# CLKB_power_regulators.net
KiCad netlist of a schematic drawn in Altium Designer
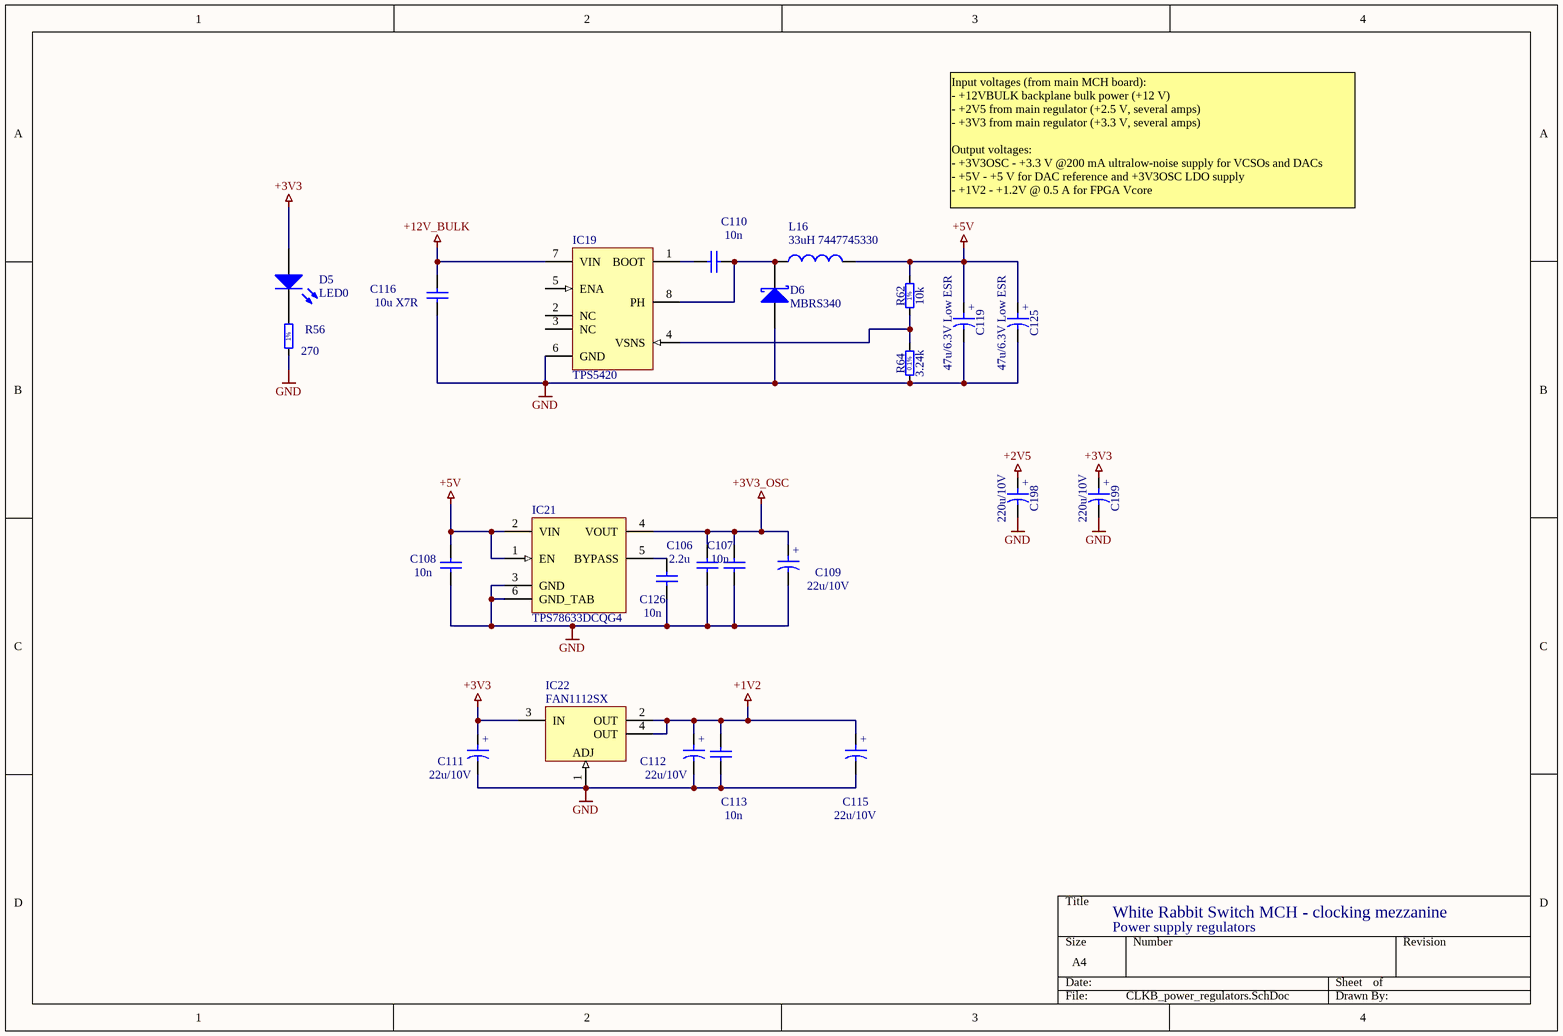
[diagram p0: CLKB_power_regulators.SchDoc]

(export (version "E")
  (design (tool "Eeschema 10.0.6"))
  (components
    (comp (ref "C106")
      (value "2.2u")
      (footprint "CAPC2012X135N")
      (description "Non-polarised capacitor")
      (fields
        (field (name "PART NUMBER") "CC0805_2.2UF_16V_10%_X7R")
        (field (name "VOLTAGE") "16V")
        (field (name "AUTHOR") "CERN DEM JLC")
      )
      (libsource (lib "Capacitors") (part "Capacitor - non polarized"))
    )
    (comp (ref "C107")
      (value "10n")
      (footprint "CAPC1608X87N")
      (description "Non-polarised capacitor")
      (fields
        (field (name "PART NUMBER") "CC0603_10NF_50V_10%_X7R")
        (field (name "VOLTAGE") "50V")
        (field (name "AUTHOR") "CERN DEM JLC")
      )
      (libsource (lib "Capacitors") (part "Capacitor - non polarized"))
    )
    (comp (ref "C108")
      (value "10n")
      (footprint "CAPC1608X87N")
      (description "Non-polarised capacitor")
      (fields
        (field (name "PART NUMBER") "CC0603_10NF_50V_10%_X7R")
        (field (name "VOLTAGE") "50V")
        (field (name "AUTHOR") "CERN DEM JLC")
      )
      (libsource (lib "Capacitors") (part "Capacitor - non polarized"))
    )
    (comp (ref "C109")
      (value "22u/10V")
      (footprint "CAPMP3216X180N")
      (description "Polarised capacitor")
      (fields
        (field (name "PART NUMBER") "CTE3216-18_22UF_10V_10%")
        (field (name "VOLTAGE") "10V")
        (field (name "AUTHOR") "CERN DEM JLC")
      )
      (libsource (lib "Capacitors") (part "Capacitor - polarized"))
    )
    (comp (ref "C110")
      (value "10n")
      (footprint "CAPC1608X87N")
      (description "Non-polarised capacitor")
      (fields
        (field (name "PART NUMBER") "CC0603_10NF_50V_10%_X7R")
        (field (name "VOLTAGE") "50V")
        (field (name "AUTHOR") "CERN DEM JLC")
      )
      (libsource (lib "Capacitors") (part "Capacitor - non polarized"))
    )
    (comp (ref "C111")
      (value "22u/10V")
      (footprint "CAPMP3216X180N")
      (description "Polarised capacitor")
      (fields
        (field (name "PART NUMBER") "CTE3216-18_22UF_10V_10%")
        (field (name "VOLTAGE") "10V")
        (field (name "AUTHOR") "CERN DEM JLC")
      )
      (libsource (lib "Capacitors") (part "Capacitor - polarized"))
    )
    (comp (ref "C112")
      (value "10n")
      (footprint "CAPC1608X87N")
      (description "Non-polarised capacitor")
      (fields
        (field (name "PART NUMBER") "CC0603_10NF_50V_10%_X7R")
        (field (name "VOLTAGE") "50V")
        (field (name "AUTHOR") "CERN DEM JLC")
      )
      (libsource (lib "Capacitors") (part "Capacitor - non polarized"))
    )
    (comp (ref "C113")
      (value "22u/10V")
      (footprint "CAPMP3216X180N")
      (description "Polarised capacitor")
      (fields
        (field (name "PART NUMBER") "CTE3216-18_22UF_10V_10%")
        (field (name "VOLTAGE") "10V")
        (field (name "AUTHOR") "CERN DEM JLC")
      )
      (libsource (lib "Capacitors") (part "Capacitor - polarized"))
    )
    (comp (ref "C115")
      (value "22u/10V")
      (footprint "CAPMP3216X180N")
      (description "Polarised capacitor")
      (fields
        (field (name "PART NUMBER") "CTE3216-18_22UF_10V_10%")
        (field (name "VOLTAGE") "10V")
        (field (name "AUTHOR") "CERN DEM JLC")
      )
      (libsource (lib "Capacitors") (part "Capacitor - polarized"))
    )
    (comp (ref "C116")
      (value "10u X7R")
      (footprint "CAPC3216X140N")
      (description "Non-polarised capacitor")
      (fields
        (field (name "PART NUMBER") "CC1206_10UF_16V_10%_X7R")
        (field (name "VOLTAGE") "16V")
        (field (name "AUTHOR") "CERN DEM JLC")
      )
      (libsource (lib "Capacitors") (part "Capacitor - non polarized"))
    )
    (comp (ref "C119")
      (value "47u/6.3V Low ESR")
      (footprint "CAPMP3528X210N")
      (description "Polarised capacitor")
      (fields
        (field (name "PART NUMBER") "CTE3528-21_47UF_6.3V_10%_LESR0250")
        (field (name "VOLTAGE") "6.3V")
        (field (name "AUTHOR") "CERN DEM JLC")
      )
      (libsource (lib "Capacitors") (part "Capacitor - polarized"))
    )
    (comp (ref "C125")
      (value "47u/6.3V Low ESR")
      (footprint "CAPMP3528X210N")
      (description "Polarised capacitor")
      (fields
        (field (name "PART NUMBER") "CTE3528-21_47UF_6.3V_10%_LESR0250")
        (field (name "VOLTAGE") "6.3V")
        (field (name "AUTHOR") "CERN DEM JLC")
      )
      (libsource (lib "Capacitors") (part "Capacitor - polarized"))
    )
    (comp (ref "C126")
      (value "10n")
      (footprint "CAPC1608X87N")
      (description "Non-polarised capacitor")
      (fields
        (field (name "PART NUMBER") "CC0603_10NF_50V_10%_X7R")
        (field (name "VOLTAGE") "50V")
        (field (name "AUTHOR") "CERN DEM JLC")
      )
      (libsource (lib "Capacitors") (part "Capacitor - non polarized"))
    )
    (comp (ref "C198")
      (value "220u/10V")
      (footprint "CAPMP7343X430N")
      (description "Polarised capacitor")
      (fields
        (field (name "PART NUMBER") "CTE7343-43_220UF_10V_10%_LESR0050")
        (field (name "VOLTAGE") "10V")
        (field (name "AUTHOR") "CERN DEM JLC")
      )
      (libsource (lib "Capacitors") (part "Capacitor - polarized"))
    )
    (comp (ref "C199")
      (value "220u/10V")
      (footprint "CAPMP7343X430N")
      (description "Polarised capacitor")
      (fields
        (field (name "PART NUMBER") "CTE7343-43_220UF_10V_10%_LESR0050")
        (field (name "VOLTAGE") "10V")
        (field (name "AUTHOR") "CERN DEM JLC")
      )
      (libsource (lib "Capacitors") (part "Capacitor - polarized"))
    )
    (comp (ref "D5")
      (value "LED0")
      (footprint "CD1608-0603")
      (description "Red chip LED")
      (fields (field (name "PUBLISHER") "Altium Limited"))
      (libsource (lib "Miscellaneous Devices") (part "LED0"))
    )
    (comp (ref "D6")
      (value "MBRS340")
      (footprint "SMB")
      (description "Schottky Diode")
      (fields (field (name "PUBLISHER") "Altium Limited"))
      (libsource (lib "wr_switch") (part "D Schottky"))
    )
    (comp (ref "IC19")
      (value "TPS5420")
      (footprint "SOIC127P600-8AL")
      (description "Step-down switchmode converter")
      (libsource (lib "wr_switch") (part "TPS5420"))
    )
    (comp (ref "IC21")
      (value "TPS78633DCQG4")
      (footprint "SOT223-6L")
      (description "TI low noise LDO, 1A load")
      (fields (field (name "Comment") "TPS78633"))
      (libsource (lib "wr_switch") (part "TPS786xx"))
    )
    (comp (ref "IC22")
      (value "FAN1112SX")
      (footprint "SOT223-4L")
      (description "Three-Terminal Adjustable Output Positive Voltage Regulator")
      (fields (field (name "PUBLISHER") "Altium Limited"))
      (libsource (lib "wr_switch") (part "1117"))
    )
    (comp (ref "L16")
      (value "33uH 7447745330")
      (footprint "L_VLCF5020")
      (description "Wuerth small footprint SMD power inductor")
      (libsource (lib "wr_switch") (part "L_WUERTH_744043"))
    )
    (comp (ref "R56")
      (value "270")
      (footprint "RESC1608X55N")
      (description "Resistor - 1%")
      (fields
        (field (name "PART NUMBER") "R0603_270R_1%_0.1W_100PPM")
        (field (name "POWER") "0.1W")
        (field (name "AUTHOR") "CERN DEM JLC")
      )
      (libsource (lib "Resistors") (part "Resistor - 1%"))
    )
    (comp (ref "R62")
      (value "10k")
      (footprint "RESC1608X55N")
      (description "Resistor - 1%")
      (fields
        (field (name "PART NUMBER") "R0603_10K_1%_0.1W_100PPM")
        (field (name "POWER") "0.1W")
        (field (name "AUTHOR") "CERN DEM JLC")
      )
      (libsource (lib "Resistors") (part "Resistor - 1%"))
    )
    (comp (ref "R64")
      (value "3.24k")
      (footprint "RESC1608X55N")
      (description "Resistor - 0.1%")
      (fields
        (field (name "PART NUMBER") "R0603_3K24_0.1%_0.063W_10PPM")
        (field (name "POWER") "0.063W")
        (field (name "AUTHOR") "CERN DEM JLC")
      )
      (libsource (lib "Resistors") (part "Resistor - 0.1%"))
    )
  )
  (nets
    (net (code "1") (name "+1V2") (class "Default")
      (node (ref "C112") (pin "2") (pinfunction "2_2") (pintype "passive"))
      (node (ref "C113") (pin "1") (pinfunction "1_1") (pintype "passive"))
      (node (ref "C115") (pin "1") (pinfunction "1_1") (pintype "passive"))
      (node (ref "IC22") (pin "2") (pinfunction "OUT_2") (pintype "power_in"))
      (node (ref "IC22") (pin "4") (pinfunction "OUT_4") (pintype "power_in"))
    )
    (net (code "2") (name "+2V5") (class "Default")
      (node (ref "C198") (pin "1") (pinfunction "1_1") (pintype "passive"))
    )
    (net (code "3") (name "+3V3") (class "Default")
      (node (ref "C111") (pin "1") (pinfunction "1_1") (pintype "passive"))
      (node (ref "C199") (pin "1") (pinfunction "1_1") (pintype "passive"))
      (node (ref "D5") (pin "1") (pinfunction "A_1") (pintype "passive"))
      (node (ref "IC22") (pin "3") (pinfunction "IN_3") (pintype "power_in"))
    )
    (net (code "4") (name "+3V3_OSC") (class "Default")
      (node (ref "C106") (pin "2") (pinfunction "2_2") (pintype "passive"))
      (node (ref "C107") (pin "2") (pinfunction "2_2") (pintype "passive"))
      (node (ref "C109") (pin "1") (pinfunction "1_1") (pintype "passive"))
      (node (ref "IC21") (pin "4") (pinfunction "VOUT_4") (pintype "power_in"))
    )
    (net (code "5") (name "+5V") (class "Default")
      (node (ref "C108") (pin "2") (pinfunction "2_2") (pintype "passive"))
      (node (ref "C119") (pin "1") (pinfunction "1_1") (pintype "passive"))
      (node (ref "C125") (pin "1") (pinfunction "1_1") (pintype "passive"))
      (node (ref "IC21") (pin "1") (pinfunction "EN_1") (pintype "input"))
      (node (ref "IC21") (pin "2") (pinfunction "VIN_2") (pintype "open_emitter"))
      (node (ref "L16") (pin "2") (pinfunction "2_2") (pintype "passive"))
      (node (ref "R62") (pin "2") (pinfunction "2_2") (pintype "passive"))
    )
    (net (code "6") (name "+12V_BULK") (class "Default")
      (node (ref "C116") (pin "2") (pinfunction "2_2") (pintype "passive"))
      (node (ref "IC19") (pin "7") (pinfunction "VIN_7") (pintype "power_in"))
    )
    (net (code "7") (name "GND") (class "Default")
      (node (ref "C106") (pin "1") (pinfunction "1_1") (pintype "passive"))
      (node (ref "C107") (pin "1") (pinfunction "1_1") (pintype "passive"))
      (node (ref "C108") (pin "1") (pinfunction "1_1") (pintype "passive"))
      (node (ref "C109") (pin "2") (pinfunction "2_2") (pintype "passive"))
      (node (ref "C111") (pin "2") (pinfunction "2_2") (pintype "passive"))
      (node (ref "C112") (pin "1") (pinfunction "1_1") (pintype "passive"))
      (node (ref "C113") (pin "2") (pinfunction "2_2") (pintype "passive"))
      (node (ref "C115") (pin "2") (pinfunction "2_2") (pintype "passive"))
      (node (ref "C116") (pin "1") (pinfunction "1_1") (pintype "passive"))
      (node (ref "C119") (pin "2") (pinfunction "2_2") (pintype "passive"))
      (node (ref "C125") (pin "2") (pinfunction "2_2") (pintype "passive"))
      (node (ref "C126") (pin "1") (pinfunction "1_1") (pintype "passive"))
      (node (ref "C198") (pin "2") (pinfunction "2_2") (pintype "passive"))
      (node (ref "C199") (pin "2") (pinfunction "2_2") (pintype "passive"))
      (node (ref "D6") (pin "1") (pinfunction "A_1") (pintype "passive"))
      (node (ref "IC19") (pin "6") (pinfunction "GND_6") (pintype "power_in"))
      (node (ref "IC21") (pin "3") (pinfunction "GND_3") (pintype "passive"))
      (node (ref "IC21") (pin "6") (pinfunction "GND_TAB_6") (pintype "passive"))
      (node (ref "IC22") (pin "1") (pinfunction "ADJ_1") (pintype "input"))
      (node (ref "R56") (pin "1") (pinfunction "1_1") (pintype "passive"))
      (node (ref "R64") (pin "1") (pinfunction "1_1") (pintype "passive"))
    )
    (net (code "8") (name "Net-(D5-K)") (class "Default")
      (node (ref "D5") (pin "2") (pinfunction "K_2") (pintype "passive"))
      (node (ref "R56") (pin "2") (pinfunction "2_2") (pintype "passive"))
    )
    (net (code "9") (name "Net-(D6-K)") (class "Default")
      (node (ref "C110") (pin "1") (pinfunction "1_1") (pintype "passive"))
      (node (ref "D6") (pin "2") (pinfunction "K_2") (pintype "passive"))
      (node (ref "IC19") (pin "8") (pinfunction "PH_8") (pintype "power_in"))
      (node (ref "L16") (pin "1") (pinfunction "1_1") (pintype "passive"))
    )
    (net (code "10") (name "Net-(IC19-BOOT)") (class "Default")
      (node (ref "C110") (pin "2") (pinfunction "2_2") (pintype "passive"))
      (node (ref "IC19") (pin "1") (pinfunction "BOOT_1") (pintype "passive"))
    )
    (net (code "11") (name "Net-(IC19-VSNS)") (class "Default")
      (node (ref "IC19") (pin "4") (pinfunction "VSNS_4") (pintype "input"))
      (node (ref "R62") (pin "1") (pinfunction "1_1") (pintype "passive"))
      (node (ref "R64") (pin "2") (pinfunction "2_2") (pintype "passive"))
    )
    (net (code "12") (name "Net-(IC21-BYPASS)") (class "Default")
      (node (ref "C126") (pin "2") (pinfunction "2_2") (pintype "passive"))
      (node (ref "IC21") (pin "5") (pinfunction "BYPASS_5") (pintype "passive"))
    )
    (net (code "13") (name "unconnected-(IC19-ENA-Pad5)") (class "Default")
      (node (ref "IC19") (pin "5") (pinfunction "ENA_5") (pintype "input"))
    )
    (net (code "14") (name "unconnected-(IC19-NC-Pad2)") (class "Default")
      (node (ref "IC19") (pin "2") (pinfunction "NC_2") (pintype "passive"))
    )
    (net (code "15") (name "unconnected-(IC19-NC-Pad3)") (class "Default")
      (node (ref "IC19") (pin "3") (pinfunction "NC_3") (pintype "passive"))
    )
  )
)
